# PoElli-Nucleo.net
KiCad netlist of a schematic drawn in EAGLE
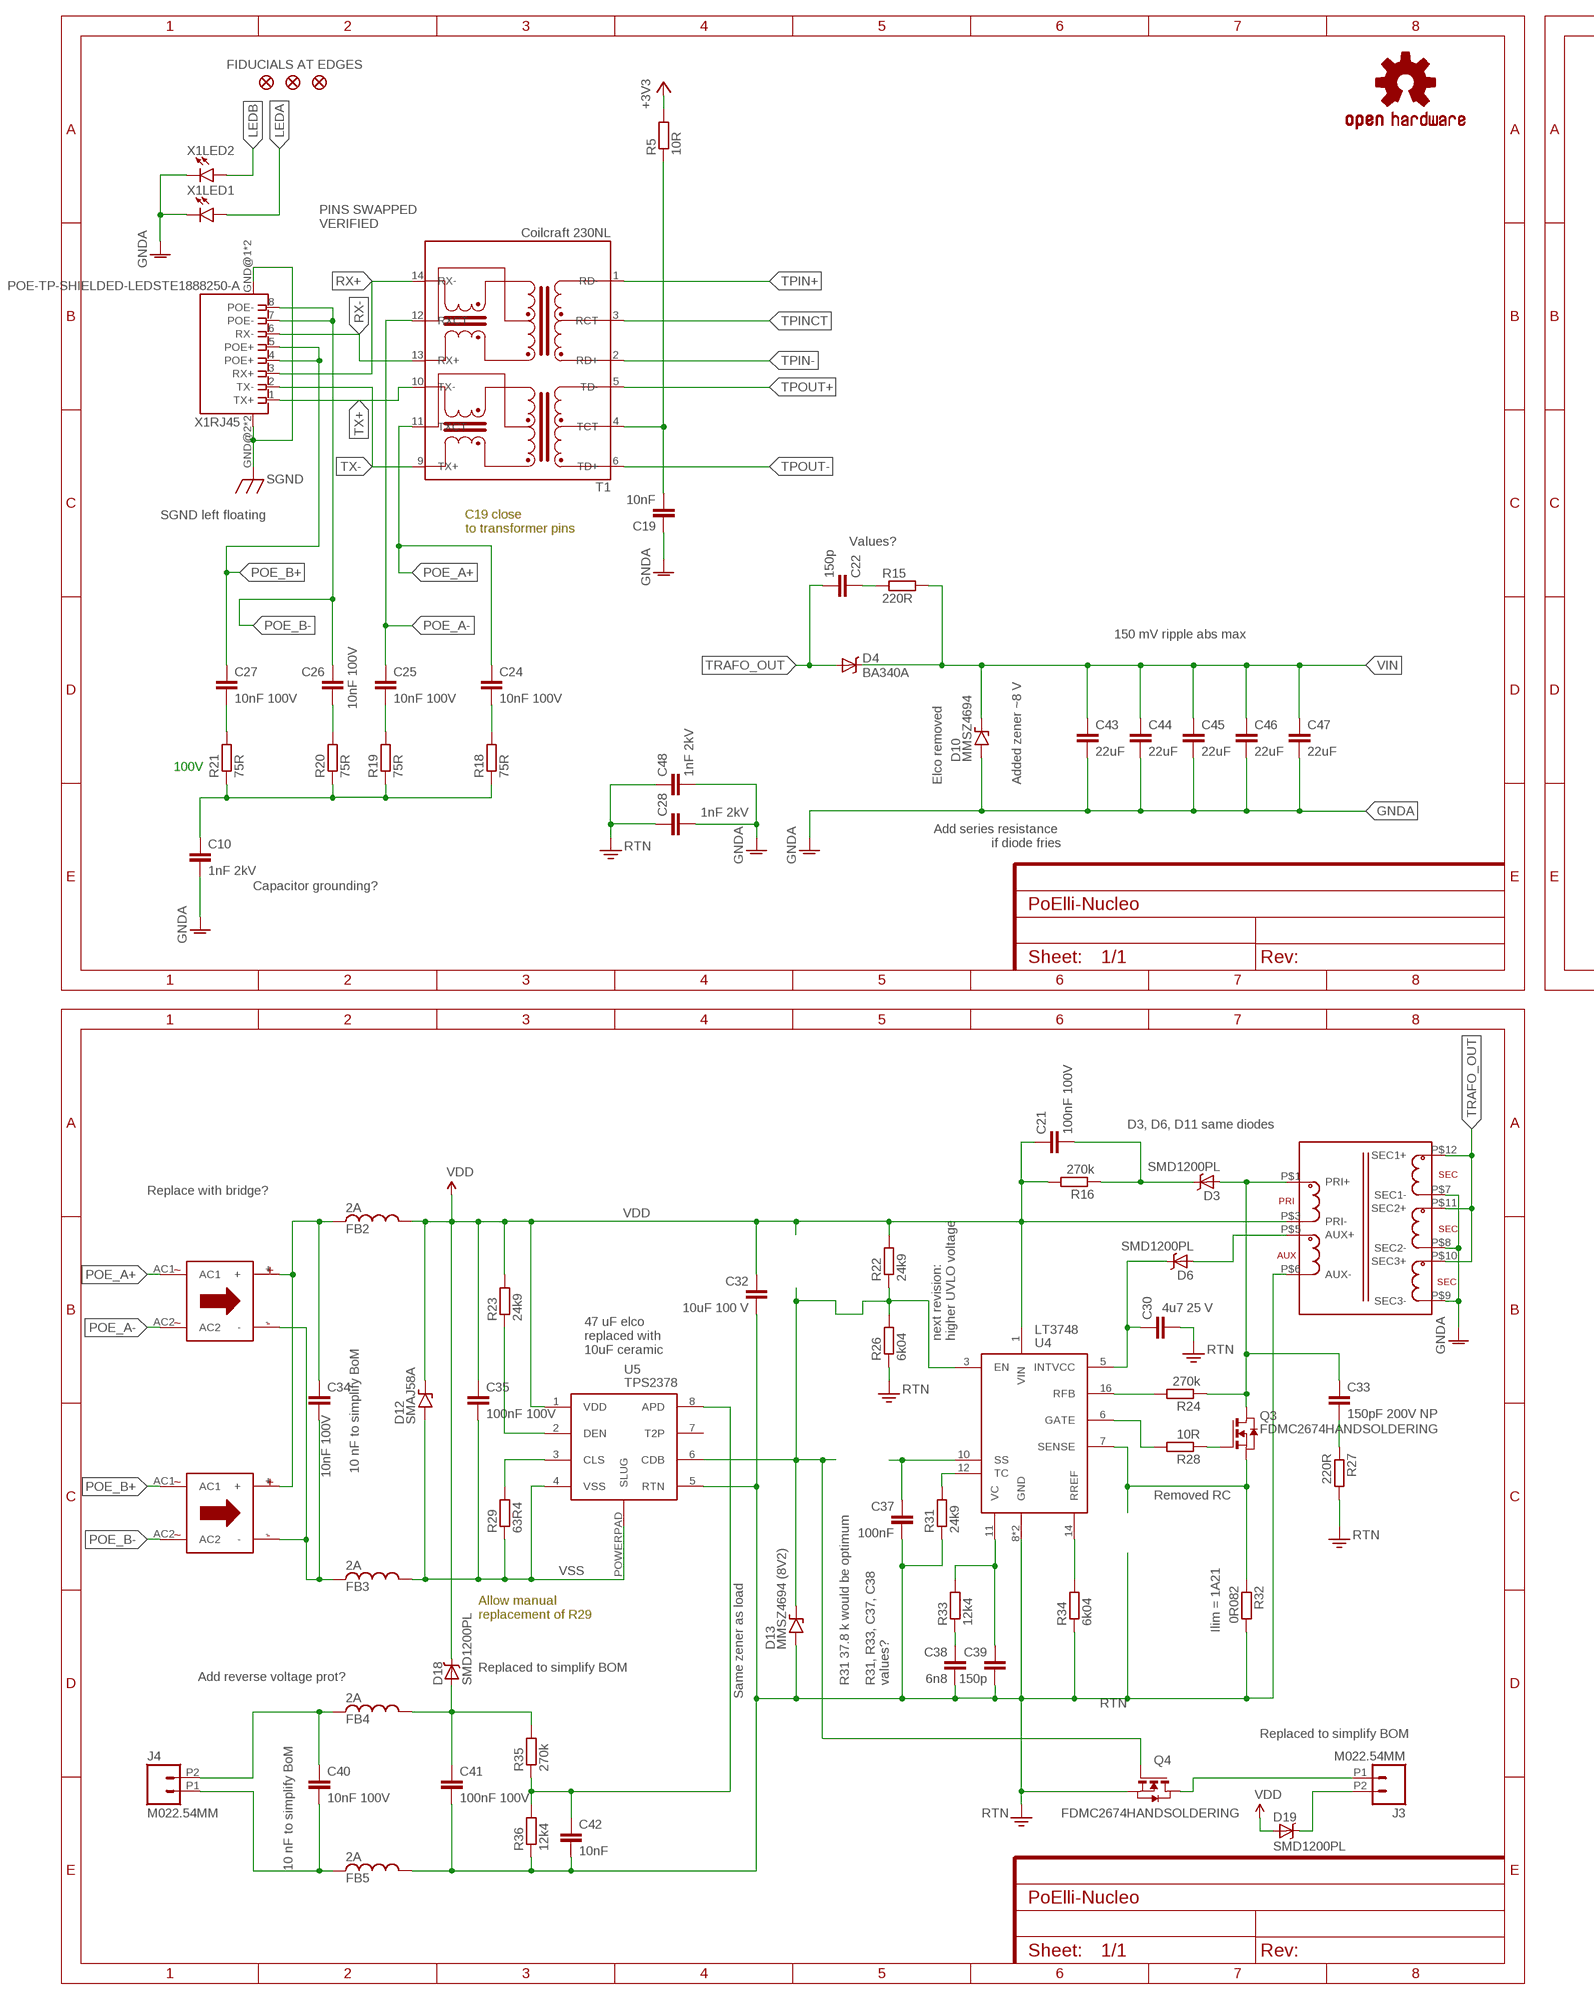
[diagram p0: schematic, sheet 1, part 1 of 2]
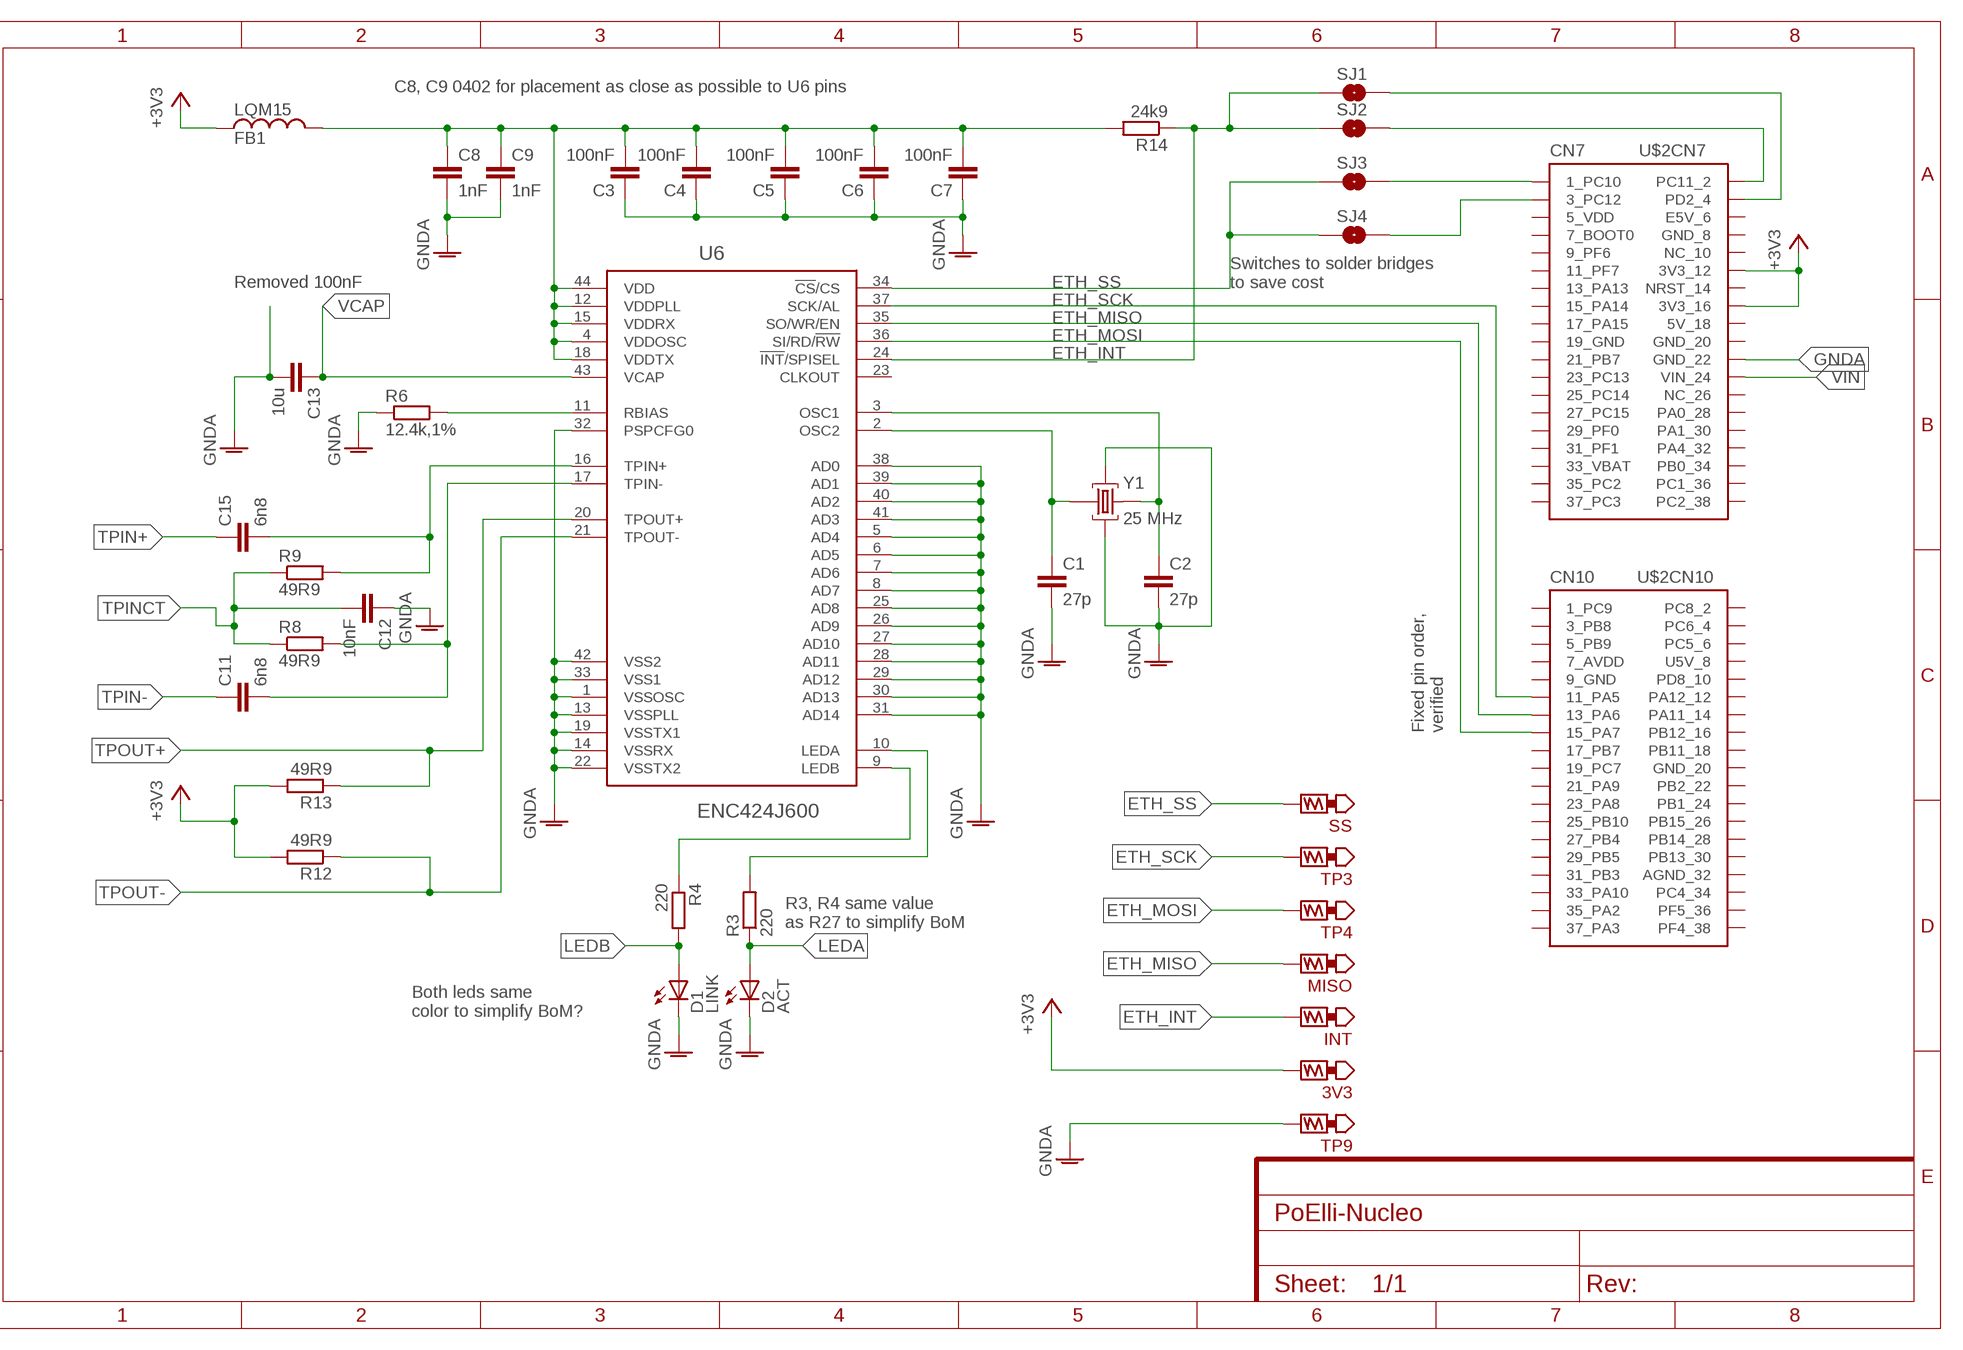
[diagram p1: schematic, sheet 1, part 2 of 2]

(export (version "E")
  (design (tool "Eeschema 10.0.6"))
  (components
    (comp (ref "3V3")
      (value "3V3")
      (footprint "eagle-import:TP_5000")
      (libsource (lib "eagle-import") (part "TEST_POINT-5000"))
    )
    (comp (ref "B1")
      (value "BRIDGE-RECTIFIER")
      (footprint "eagle-import:MBS1")
      (libsource (lib "eagle-import") (part "BRIDGE-RECTIFIER"))
    )
    (comp (ref "B2")
      (value "BRIDGE-RECTIFIER")
      (footprint "eagle-import:MBS1")
      (libsource (lib "eagle-import") (part "BRIDGE-RECTIFIER"))
    )
    (comp (ref "C1")
      (value "27p")
      (footprint "eagle-import:SMD0603-B")
      (libsource (lib "eagle-import") (part "C0603-B"))
    )
    (comp (ref "C2")
      (value "27p")
      (footprint "eagle-import:SMD0603-B")
      (libsource (lib "eagle-import") (part "C0603-B"))
    )
    (comp (ref "C3")
      (value "100nF")
      (footprint "eagle-import:SMD0603-B")
      (libsource (lib "eagle-import") (part "C0603-B"))
    )
    (comp (ref "C4")
      (value "100nF")
      (footprint "eagle-import:SMD0603-B")
      (libsource (lib "eagle-import") (part "C0603-B"))
    )
    (comp (ref "C5")
      (value "100nF")
      (footprint "eagle-import:SMD0603-B")
      (libsource (lib "eagle-import") (part "C0603-B"))
    )
    (comp (ref "C6")
      (value "100nF")
      (footprint "eagle-import:SMD0603-B")
      (libsource (lib "eagle-import") (part "C0603-B"))
    )
    (comp (ref "C7")
      (value "100nF")
      (footprint "eagle-import:SMD0603-B")
      (libsource (lib "eagle-import") (part "C0603-B"))
    )
    (comp (ref "C8")
      (value "1nF")
      (footprint "eagle-import:SMD0402-B")
      (libsource (lib "eagle-import") (part "C0402-B"))
    )
    (comp (ref "C9")
      (value "1nF")
      (footprint "eagle-import:SMD0402-B")
      (libsource (lib "eagle-import") (part "C0402-B"))
    )
    (comp (ref "C10")
      (value "1nF 2kV")
      (footprint "eagle-import:SMD1206-A")
      (libsource (lib "eagle-import") (part "C1206-A"))
    )
    (comp (ref "C11")
      (value "6n8")
      (footprint "eagle-import:SMD0603-B")
      (libsource (lib "eagle-import") (part "C0603-B"))
    )
    (comp (ref "C12")
      (value "10nF")
      (footprint "eagle-import:SMD0603-B")
      (libsource (lib "eagle-import") (part "C0603-B"))
    )
    (comp (ref "C13")
      (value "10u")
      (footprint "eagle-import:SMD0603-B")
      (libsource (lib "eagle-import") (part "C0603-B"))
    )
    (comp (ref "C15")
      (value "6n8")
      (footprint "eagle-import:SMD0603-B")
      (libsource (lib "eagle-import") (part "C0603-B"))
    )
    (comp (ref "C19")
      (value "10nF")
      (footprint "eagle-import:SMD0603-B")
      (libsource (lib "eagle-import") (part "C0603-B"))
    )
    (comp (ref "C21")
      (value "100nF 100V")
      (footprint "eagle-import:SMD0603-B")
      (libsource (lib "eagle-import") (part "C0603-B"))
    )
    (comp (ref "C22")
      (value "150p")
      (footprint "eagle-import:SMD0603-B")
      (libsource (lib "eagle-import") (part "C0603-B"))
    )
    (comp (ref "C24")
      (value "10nF 100V")
      (footprint "eagle-import:SMD0603-B")
      (libsource (lib "eagle-import") (part "C0603-B"))
    )
    (comp (ref "C25")
      (value "10nF 100V")
      (footprint "eagle-import:SMD0603-B")
      (libsource (lib "eagle-import") (part "C0603-B"))
    )
    (comp (ref "C26")
      (value "10nF 100V")
      (footprint "eagle-import:SMD0603-B")
      (libsource (lib "eagle-import") (part "C0603-B"))
    )
    (comp (ref "C27")
      (value "10nF 100V")
      (footprint "eagle-import:SMD0603-B")
      (libsource (lib "eagle-import") (part "C0603-B"))
    )
    (comp (ref "C28")
      (value "1nF 2kV")
      (footprint "eagle-import:SMD1206-A")
      (libsource (lib "eagle-import") (part "C1206-A"))
    )
    (comp (ref "C30")
      (value "4u7 25 V")
      (footprint "eagle-import:SMD0603-B")
      (libsource (lib "eagle-import") (part "C0603-B"))
    )
    (comp (ref "C32")
      (value "10uF 100 V")
      (footprint "eagle-import:SMD2220-REFLOW")
      (libsource (lib "eagle-import") (part "C2220-REFLOW"))
    )
    (comp (ref "C33")
      (value "150pF 200V NP")
      (footprint "eagle-import:SMD0603-B")
      (libsource (lib "eagle-import") (part "C0603-B"))
    )
    (comp (ref "C34")
      (value "10nF 100V")
      (footprint "eagle-import:SMD0603-B")
      (libsource (lib "eagle-import") (part "C0603-B"))
    )
    (comp (ref "C35")
      (value "100nF 100V")
      (footprint "eagle-import:SMD0603-B")
      (libsource (lib "eagle-import") (part "C0603-B"))
    )
    (comp (ref "C37")
      (value "100nF")
      (footprint "eagle-import:SMD0603-B")
      (libsource (lib "eagle-import") (part "C0603-B"))
    )
    (comp (ref "C38")
      (value "6n8")
      (footprint "eagle-import:SMD0603-B")
      (libsource (lib "eagle-import") (part "C0603-B"))
    )
    (comp (ref "C39")
      (value "150p")
      (footprint "eagle-import:SMD0603-B")
      (libsource (lib "eagle-import") (part "C0603-B"))
    )
    (comp (ref "C40")
      (value "10nF 100V")
      (footprint "eagle-import:SMD0603-B")
      (libsource (lib "eagle-import") (part "C0603-B"))
    )
    (comp (ref "C41")
      (value "100nF 100V")
      (footprint "eagle-import:SMD0603-B")
      (libsource (lib "eagle-import") (part "C0603-B"))
    )
    (comp (ref "C42")
      (value "10nF")
      (footprint "eagle-import:SMD0603-B")
      (libsource (lib "eagle-import") (part "C0603-B"))
    )
    (comp (ref "C43")
      (value "22uF")
      (footprint "eagle-import:SMD1206-A")
      (libsource (lib "eagle-import") (part "C1206-A"))
    )
    (comp (ref "C44")
      (value "22uF")
      (footprint "eagle-import:SMD1206-A")
      (libsource (lib "eagle-import") (part "C1206-A"))
    )
    (comp (ref "C45")
      (value "22uF")
      (footprint "eagle-import:SMD1206-A")
      (libsource (lib "eagle-import") (part "C1206-A"))
    )
    (comp (ref "C46")
      (value "22uF")
      (footprint "eagle-import:SMD1206-A")
      (libsource (lib "eagle-import") (part "C1206-A"))
    )
    (comp (ref "C47")
      (value "22uF")
      (footprint "eagle-import:SMD1206-A")
      (libsource (lib "eagle-import") (part "C1206-A"))
    )
    (comp (ref "C48")
      (value "1nF 2kV")
      (footprint "eagle-import:SMD1206-A")
      (libsource (lib "eagle-import") (part "C1206-A"))
    )
    (comp (ref "D1")
      (value "LINK")
      (footprint "eagle-import:LED-0603")
      (libsource (lib "eagle-import") (part "LED-GREEN0603"))
    )
    (comp (ref "D2")
      (value "ACT")
      (footprint "eagle-import:LED-0603")
      (libsource (lib "eagle-import") (part "LED-YELLOW0603"))
    )
    (comp (ref "D3")
      (value "SMD1200PL")
      (footprint "eagle-import:SOD-123FL-A")
      (libsource (lib "eagle-import") (part "SMD1XXPL"))
    )
    (comp (ref "D4")
      (value "BA340A")
      (footprint "eagle-import:SMA-DIODE")
      (libsource (lib "eagle-import") (part "B340A"))
    )
    (comp (ref "D6")
      (value "SMD1200PL")
      (footprint "eagle-import:SOD-123FL-A")
      (libsource (lib "eagle-import") (part "SMD1XXPL"))
    )
    (comp (ref "D10")
      (value "MMSZ4694")
      (footprint "eagle-import:SOD-123FL-A")
      (libsource (lib "eagle-import") (part "MMSZ4XXX"))
    )
    (comp (ref "D12")
      (value "SMAJ58A")
      (footprint "eagle-import:SMA")
      (libsource (lib "eagle-import") (part "SMAJ58A"))
    )
    (comp (ref "D13")
      (value "MMSZ4694 (8V2)")
      (footprint "eagle-import:SOD-123FL-A")
      (libsource (lib "eagle-import") (part "MMSZ4XXX"))
    )
    (comp (ref "D18")
      (value "SMD1200PL")
      (footprint "eagle-import:SOD-123FL-A")
      (libsource (lib "eagle-import") (part "SMD1XXPL"))
    )
    (comp (ref "D19")
      (value "SMD1200PL")
      (footprint "eagle-import:SOD-123FL-A")
      (libsource (lib "eagle-import") (part "SMD1XXPL"))
    )
    (comp (ref "FB1")
      (value "LQM15")
      (footprint "eagle-import:SMD0603-A")
      (libsource (lib "eagle-import") (part "FB-0603-A"))
    )
    (comp (ref "FB2")
      (value "2A")
      (footprint "eagle-import:SMD0603-A")
      (libsource (lib "eagle-import") (part "FB-0603-A"))
    )
    (comp (ref "FB3")
      (value "2A")
      (footprint "eagle-import:SMD0603-A")
      (libsource (lib "eagle-import") (part "FB-0603-A"))
    )
    (comp (ref "FB4")
      (value "2A")
      (footprint "eagle-import:SMD0603-A")
      (libsource (lib "eagle-import") (part "FB-0603-A"))
    )
    (comp (ref "FB5")
      (value "2A")
      (footprint "eagle-import:SMD0603-A")
      (libsource (lib "eagle-import") (part "FB-0603-A"))
    )
    (comp (ref "FID1")
      (value "FIDUCIAL1X2")
      (footprint "eagle-import:FIDUCIAL-1X2")
      (libsource (lib "eagle-import") (part "FIDUCIAL1X2"))
    )
    (comp (ref "FID2")
      (value "FIDUCIAL1X2")
      (footprint "eagle-import:FIDUCIAL-1X2")
      (libsource (lib "eagle-import") (part "FIDUCIAL1X2"))
    )
    (comp (ref "FID3")
      (value "FIDUCIAL1X2")
      (footprint "eagle-import:FIDUCIAL-1X2")
      (libsource (lib "eagle-import") (part "FIDUCIAL1X2"))
    )
    (comp (ref "INT")
      (value "TEST_POINT-5000")
      (footprint "eagle-import:TP_5000")
      (libsource (lib "eagle-import") (part "TEST_POINT-5000"))
    )
    (comp (ref "J3")
      (value "M022.54MM")
      (footprint "eagle-import:1X02_2.54_SCREWTERM")
      (libsource (lib "eagle-import") (part "M022.54MM_SCREWTERM"))
    )
    (comp (ref "J4")
      (value "M022.54MM")
      (footprint "eagle-import:1X02_2.54_SCREWTERM")
      (libsource (lib "eagle-import") (part "M022.54MM_SCREWTERM"))
    )
    (comp (ref "LOGO1")
      (value "OSHW-LOGOM")
      (footprint "eagle-import:OSHW-LOGO-M")
      (libsource (lib "eagle-import") (part "OSHW-LOGOM"))
    )
    (comp (ref "MISO")
      (value "MISO")
      (footprint "eagle-import:TP_5021")
      (libsource (lib "eagle-import") (part "TEST_POINT-5021"))
    )
    (comp (ref "Q3")
      (value "FDMC2674HANDSOLDERING")
      (footprint "eagle-import:MLP8L33_HS")
      (libsource (lib "eagle-import") (part "FDMC2674HANDSOLDERING"))
    )
    (comp (ref "Q4")
      (value "FDMC2674HANDSOLDERING")
      (footprint "eagle-import:MLP8L33_HS")
      (libsource (lib "eagle-import") (part "FDMC2674HANDSOLDERING"))
    )
    (comp (ref "R3")
      (value "220")
      (footprint "eagle-import:SMD0603-A")
      (libsource (lib "eagle-import") (part "R0603-A"))
    )
    (comp (ref "R4")
      (value "220")
      (footprint "eagle-import:SMD0603-A")
      (libsource (lib "eagle-import") (part "R0603-A"))
    )
    (comp (ref "R5")
      (value "10R")
      (footprint "eagle-import:SMD0603-B")
      (libsource (lib "eagle-import") (part "R0603-B"))
    )
    (comp (ref "R6")
      (value "12.4k,1%")
      (footprint "eagle-import:SMD0603-B")
      (libsource (lib "eagle-import") (part "R0603-B"))
    )
    (comp (ref "R8")
      (value "49R9")
      (footprint "eagle-import:SMD0603-B")
      (libsource (lib "eagle-import") (part "R0603-B"))
    )
    (comp (ref "R9")
      (value "49R9")
      (footprint "eagle-import:SMD0603-B")
      (libsource (lib "eagle-import") (part "R0603-B"))
    )
    (comp (ref "R12")
      (value "49R9")
      (footprint "eagle-import:SMD0603-B")
      (libsource (lib "eagle-import") (part "R0603-B"))
    )
    (comp (ref "R13")
      (value "49R9")
      (footprint "eagle-import:SMD0603-B")
      (libsource (lib "eagle-import") (part "R0603-B"))
    )
    (comp (ref "R14")
      (value "24k9")
      (footprint "eagle-import:SMD0603-A")
      (libsource (lib "eagle-import") (part "R0603-A"))
    )
    (comp (ref "R15")
      (value "220R")
      (footprint "eagle-import:SMD0603-B")
      (libsource (lib "eagle-import") (part "R0603-B"))
    )
    (comp (ref "R16")
      (value "270k")
      (footprint "eagle-import:SMD0603-A")
      (libsource (lib "eagle-import") (part "R0603-A"))
    )
    (comp (ref "R18")
      (value "75R")
      (footprint "eagle-import:SMD0603-B")
      (libsource (lib "eagle-import") (part "R0603-B"))
    )
    (comp (ref "R19")
      (value "75R")
      (footprint "eagle-import:SMD0603-B")
      (libsource (lib "eagle-import") (part "R0603-B"))
    )
    (comp (ref "R20")
      (value "75R")
      (footprint "eagle-import:SMD0603-B")
      (libsource (lib "eagle-import") (part "R0603-B"))
    )
    (comp (ref "R21")
      (value "75R")
      (footprint "eagle-import:SMD0603-B")
      (libsource (lib "eagle-import") (part "R0603-B"))
    )
    (comp (ref "R22")
      (value "24k9")
      (footprint "eagle-import:SMD0603-B")
      (libsource (lib "eagle-import") (part "R0603-B"))
    )
    (comp (ref "R23")
      (value "24k9")
      (footprint "eagle-import:SMD0603-B")
      (libsource (lib "eagle-import") (part "R0603-B"))
    )
    (comp (ref "R24")
      (value "270k")
      (footprint "eagle-import:SMD0603-B")
      (libsource (lib "eagle-import") (part "R0603-B"))
    )
    (comp (ref "R26")
      (value "6k04")
      (footprint "eagle-import:SMD0603-B")
      (libsource (lib "eagle-import") (part "R0603-B"))
    )
    (comp (ref "R27")
      (value "220R")
      (footprint "eagle-import:SMD0603-B")
      (libsource (lib "eagle-import") (part "R0603-B"))
    )
    (comp (ref "R28")
      (value "10R")
      (footprint "eagle-import:SMD0603-B")
      (libsource (lib "eagle-import") (part "R0603-B"))
    )
    (comp (ref "R29")
      (value "63R4")
      (footprint "eagle-import:SMD0603-B")
      (libsource (lib "eagle-import") (part "R0603-B"))
    )
    (comp (ref "R31")
      (value "24k9")
      (footprint "eagle-import:SMD0603-B")
      (libsource (lib "eagle-import") (part "R0603-B"))
    )
    (comp (ref "R32")
      (value "0R082")
      (footprint "eagle-import:SMD0603-B")
      (libsource (lib "eagle-import") (part "R0603-B"))
    )
    (comp (ref "R33")
      (value "12k4")
      (footprint "eagle-import:SMD0603-B")
      (libsource (lib "eagle-import") (part "R0603-B"))
    )
    (comp (ref "R34")
      (value "6k04")
      (footprint "eagle-import:SMD0603-B")
      (libsource (lib "eagle-import") (part "R0603-B"))
    )
    (comp (ref "R35")
      (value "270k")
      (footprint "eagle-import:SMD0603-B")
      (libsource (lib "eagle-import") (part "R0603-B"))
    )
    (comp (ref "R36")
      (value "12k4")
      (footprint "eagle-import:SMD0603-B")
      (libsource (lib "eagle-import") (part "R0603-B"))
    )
    (comp (ref "SJ1")
      (value "SOLDERJUMPERNC2")
      (footprint "eagle-import:SJ_2S-NOTRACE")
      (libsource (lib "eagle-import") (part "SOLDERJUMPERNC2"))
    )
    (comp (ref "SJ2")
      (value "SOLDERJUMPERNO")
      (footprint "eagle-import:SJ_2S-NO")
      (libsource (lib "eagle-import") (part "SOLDERJUMPERNO"))
    )
    (comp (ref "SJ3")
      (value "SOLDERJUMPERNC2")
      (footprint "eagle-import:SJ_2S-NOTRACE")
      (libsource (lib "eagle-import") (part "SOLDERJUMPERNC2"))
    )
    (comp (ref "SJ4")
      (value "SOLDERJUMPERNO")
      (footprint "eagle-import:SJ_2S-NO")
      (libsource (lib "eagle-import") (part "SOLDERJUMPERNO"))
    )
    (comp (ref "SS")
      (value "SS")
      (footprint "eagle-import:TP_5021")
      (libsource (lib "eagle-import") (part "TEST_POINT-5021"))
    )
    (comp (ref "T1")
      (value "Coilcraft 230NL")
      (footprint "eagle-import:COILCRAFT-ETH1-230L")
      (libsource (lib "eagle-import") (part "POE-ISOLATION-230NL"))
    )
    (comp (ref "T2")
      (value "FLYBACK-3_OUTPUTS_749119350")
      (footprint "eagle-import:WE_749119350")
      (libsource (lib "eagle-import") (part "FLYBACK-3_OUTPUTS_749119350"))
    )
    (comp (ref "TP3")
      (value "SCK")
      (footprint "eagle-import:TP_5021")
      (libsource (lib "eagle-import") (part "TEST_POINT-5021"))
    )
    (comp (ref "TP4")
      (value "MOSI")
      (footprint "eagle-import:TP_5021")
      (libsource (lib "eagle-import") (part "TEST_POINT-5021"))
    )
    (comp (ref "TP9")
      (value "GND")
      (footprint "eagle-import:TP_5000")
      (libsource (lib "eagle-import") (part "TEST_POINT-5000"))
    )
    (comp (ref "U$2")
      (value "NUCLEO-SHIELD-20PIN")
      (footprint "eagle-import:NUCLEO-SHIELD-UNDERSIDE-SHORT-20-PINHEADER")
      (libsource (lib "eagle-import") (part "NUCLEO-SHIELD-20PIN"))
    )
    (comp (ref "U4")
      (value "LT3748")
      (footprint "eagle-import:MSOP16(12)")
      (libsource (lib "eagle-import") (part "LT3748"))
    )
    (comp (ref "U5")
      (value "TPS2378")
      (footprint "eagle-import:SO08-POWERPAD")
      (libsource (lib "eagle-import") (part "TPS2378"))
    )
    (comp (ref "U6")
      (value "ENC424J600")
      (footprint "eagle-import:TQFP44-0.8MM")
      (libsource (lib "eagle-import") (part "ENC424J600"))
    )
    (comp (ref "X1")
      (value "POE-TP-SHIELDED-LEDSTE1888250-A")
      (footprint "eagle-import:TE1888250-A")
      (libsource (lib "eagle-import") (part "POE-TP-SHIELDED-LEDSTE1888250-A"))
    )
    (comp (ref "Y1")
      (value "25 MHz")
      (footprint "eagle-import:CRYSTAL-SMD-3225-GND")
      (libsource (lib "eagle-import") (part "CRYSTAL_WITH_GND"))
    )
  )
  (nets
    (net (code "1") (name "+3V3") (class "Default")
      (node (ref "3V3") (pin "P$1") (pinfunction "P$1_P$1") (pintype "passive"))
      (node (ref "FB1") (pin "P$1") (pinfunction "1_P$1") (pintype "passive"))
      (node (ref "R12") (pin "P$2") (pinfunction "2_P$2") (pintype "passive"))
      (node (ref "R13") (pin "P$2") (pinfunction "2_P$2") (pintype "passive"))
      (node (ref "R5") (pin "P$2") (pinfunction "2_P$2") (pintype "passive"))
      (node (ref "U$2") (pin "CN7_12") (pinfunction "3V3_12_CN7_12") (pintype "bidirectional"))
      (node (ref "U$2") (pin "CN7_16") (pinfunction "3V3_16_CN7_16") (pintype "bidirectional"))
    )
    (net (code "2") (name "/VSS") (class "Default")
      (node (ref "C35") (pin "P$2") (pinfunction "2_P$2") (pintype "passive"))
      (node (ref "D12") (pin "A") (pinfunction "A_A") (pintype "passive"))
      (node (ref "FB3") (pin "P$2") (pinfunction "2_P$2") (pintype "passive"))
      (node (ref "R29") (pin "P$1") (pinfunction "1_P$1") (pintype "passive"))
      (node (ref "U5") (pin "4") (pinfunction "VSS_4") (pintype "power_in"))
      (node (ref "U5") (pin "POWERPAD") (pinfunction "SLUG_POWERPAD") (pintype "power_in"))
    )
    (net (code "3") (name "ETH_INT") (class "Default")
      (node (ref "INT") (pin "P$1") (pinfunction "P$1_P$1") (pintype "passive"))
      (node (ref "R14") (pin "P$1") (pinfunction "1_P$1") (pintype "passive"))
      (node (ref "SJ1") (pin "1") (pinfunction "1_1") (pintype "passive"))
      (node (ref "SJ2") (pin "1") (pinfunction "1_1") (pintype "passive"))
      (node (ref "U6") (pin "24") (pinfunction "~{INT}/SPISEL_24") (pintype "bidirectional"))
    )
    (net (code "4") (name "ETH_MISO") (class "Default")
      (node (ref "MISO") (pin "P$1") (pinfunction "P$1_P$1") (pintype "passive"))
      (node (ref "U$2") (pin "CN10_13") (pinfunction "13_PA6_CN10_13") (pintype "bidirectional"))
      (node (ref "U6") (pin "35") (pinfunction "SO/WR/EN_35") (pintype "bidirectional"))
    )
    (net (code "5") (name "ETH_MOSI") (class "Default")
      (node (ref "TP4") (pin "P$1") (pinfunction "P$1_P$1") (pintype "passive"))
      (node (ref "U$2") (pin "CN10_15") (pinfunction "15_PA7_CN10_15") (pintype "bidirectional"))
      (node (ref "U6") (pin "36") (pinfunction "SI/RD/~{RW}_36") (pintype "input"))
    )
    (net (code "6") (name "ETH_SCK") (class "Default")
      (node (ref "TP3") (pin "P$1") (pinfunction "P$1_P$1") (pintype "passive"))
      (node (ref "U$2") (pin "CN10_11") (pinfunction "11_PA5_CN10_11") (pintype "bidirectional"))
      (node (ref "U6") (pin "37") (pinfunction "SCK/AL_37") (pintype "input"))
    )
    (net (code "7") (name "ETH_SS") (class "Default")
      (node (ref "SJ3") (pin "1") (pinfunction "1_1") (pintype "passive"))
      (node (ref "SJ4") (pin "1") (pinfunction "1_1") (pintype "passive"))
      (node (ref "SS") (pin "P$1") (pinfunction "P$1_P$1") (pintype "passive"))
      (node (ref "U6") (pin "34") (pinfunction "~{CS}/CS_34") (pintype "input"))
    )
    (net (code "8") (name "GNDA") (class "Default")
      (node (ref "C1") (pin "P$2") (pinfunction "2_P$2") (pintype "passive"))
      (node (ref "C10") (pin "P$2") (pinfunction "2_P$2") (pintype "passive"))
      (node (ref "C12") (pin "P$1") (pinfunction "1_P$1") (pintype "passive"))
      (node (ref "C13") (pin "P$2") (pinfunction "2_P$2") (pintype "passive"))
      (node (ref "C19") (pin "P$1") (pinfunction "1_P$1") (pintype "passive"))
      (node (ref "C2") (pin "P$2") (pinfunction "2_P$2") (pintype "passive"))
      (node (ref "C28") (pin "P$2") (pinfunction "2_P$2") (pintype "passive"))
      (node (ref "C3") (pin "P$1") (pinfunction "1_P$1") (pintype "passive"))
      (node (ref "C4") (pin "P$1") (pinfunction "1_P$1") (pintype "passive"))
      (node (ref "C43") (pin "P$2") (pinfunction "2_P$2") (pintype "passive"))
      (node (ref "C44") (pin "P$2") (pinfunction "2_P$2") (pintype "passive"))
      (node (ref "C45") (pin "P$2") (pinfunction "2_P$2") (pintype "passive"))
      (node (ref "C46") (pin "P$2") (pinfunction "2_P$2") (pintype "passive"))
      (node (ref "C47") (pin "P$2") (pinfunction "2_P$2") (pintype "passive"))
      (node (ref "C48") (pin "P$2") (pinfunction "2_P$2") (pintype "passive"))
      (node (ref "C5") (pin "P$1") (pinfunction "1_P$1") (pintype "passive"))
      (node (ref "C6") (pin "P$1") (pinfunction "1_P$1") (pintype "passive"))
      (node (ref "C7") (pin "P$1") (pinfunction "1_P$1") (pintype "passive"))
      (node (ref "C8") (pin "2") (pinfunction "2_2") (pintype "passive"))
      (node (ref "C9") (pin "2") (pinfunction "2_2") (pintype "passive"))
      (node (ref "D1") (pin "C") (pinfunction "C_C") (pintype "passive"))
      (node (ref "D10") (pin "A") (pinfunction "A_A") (pintype "passive"))
      (node (ref "D2") (pin "C") (pinfunction "C_C") (pintype "passive"))
      (node (ref "R6") (pin "P$1") (pinfunction "1_P$1") (pintype "passive"))
      (node (ref "T2") (pin "P$7") (pinfunction "SEC1-_P$7") (pintype "bidirectional"))
      (node (ref "T2") (pin "P$8") (pinfunction "SEC2-_P$8") (pintype "bidirectional"))
      (node (ref "T2") (pin "P$9") (pinfunction "SEC3-_P$9") (pintype "bidirectional"))
      (node (ref "TP9") (pin "P$1") (pinfunction "P$1_P$1") (pintype "passive"))
      (node (ref "U$2") (pin "CN7_22") (pinfunction "GND_22_CN7_22") (pintype "bidirectional"))
      (node (ref "U6") (pin "1") (pinfunction "VSSOSC_1") (pintype "power_in"))
      (node (ref "U6") (pin "13") (pinfunction "VSSPLL_13") (pintype "power_in"))
      (node (ref "U6") (pin "14") (pinfunction "VSSRX_14") (pintype "power_in"))
      (node (ref "U6") (pin "19") (pinfunction "VSSTX1_19") (pintype "power_in"))
      (node (ref "U6") (pin "22") (pinfunction "VSSTX2_22") (pintype "power_in"))
      (node (ref "U6") (pin "25") (pinfunction "AD8_25") (pintype "bidirectional"))
      (node (ref "U6") (pin "26") (pinfunction "AD9_26") (pintype "bidirectional"))
      (node (ref "U6") (pin "27") (pinfunction "AD10_27") (pintype "bidirectional"))
      (node (ref "U6") (pin "28") (pinfunction "AD11_28") (pintype "bidirectional"))
      (node (ref "U6") (pin "29") (pinfunction "AD12_29") (pintype "bidirectional"))
      (node (ref "U6") (pin "30") (pinfunction "AD13_30") (pintype "bidirectional"))
      (node (ref "U6") (pin "31") (pinfunction "AD14_31") (pintype "bidirectional"))
      (node (ref "U6") (pin "32") (pinfunction "PSPCFG0_32") (pintype "input"))
      (node (ref "U6") (pin "33") (pinfunction "VSS1_33") (pintype "power_in"))
      (node (ref "U6") (pin "38") (pinfunction "AD0_38") (pintype "bidirectional"))
      (node (ref "U6") (pin "39") (pinfunction "AD1_39") (pintype "bidirectional"))
      (node (ref "U6") (pin "40") (pinfunction "AD2_40") (pintype "bidirectional"))
      (node (ref "U6") (pin "41") (pinfunction "AD3_41") (pintype "bidirectional"))
      (node (ref "U6") (pin "42") (pinfunction "VSS2_42") (pintype "power_in"))
      (node (ref "U6") (pin "5") (pinfunction "AD4_5") (pintype "bidirectional"))
      (node (ref "U6") (pin "6") (pinfunction "AD5_6") (pintype "bidirectional"))
      (node (ref "U6") (pin "7") (pinfunction "AD6_7") (pintype "bidirectional"))
      (node (ref "U6") (pin "8") (pinfunction "AD7_8") (pintype "bidirectional"))
      (node (ref "X1") (pin "12") (pinfunction "C_12") (pintype "passive"))
      (node (ref "X1") (pin "9") (pinfunction "C_9") (pintype "passive"))
      (node (ref "Y1") (pin "2") (pinfunction "GND_2") (pintype "passive"))
      (node (ref "Y1") (pin "4") (pinfunction "GND_4") (pintype "passive"))
    )
    (net (code "9") (name "LEDA") (class "Default")
      (node (ref "D2") (pin "A") (pinfunction "A_A") (pintype "passive"))
      (node (ref "R3") (pin "P$1") (pinfunction "1_P$1") (pintype "passive"))
      (node (ref "X1") (pin "10") (pinfunction "A_10") (pintype "passive"))
    )
    (net (code "10") (name "LEDB") (class "Default")
      (node (ref "D1") (pin "A") (pinfunction "A_A") (pintype "passive"))
      (node (ref "R4") (pin "P$2") (pinfunction "2_P$2") (pintype "passive"))
      (node (ref "X1") (pin "11") (pinfunction "A_11") (pintype "passive"))
    )
    (net (code "11") (name "Net-(C1-1)") (class "Default")
      (node (ref "C1") (pin "P$1") (pinfunction "1_P$1") (pintype "passive"))
      (node (ref "U6") (pin "2") (pinfunction "OSC2_2") (pintype "output"))
      (node (ref "Y1") (pin "1") (pinfunction "C1_1") (pintype "passive"))
    )
    (net (code "12") (name "Net-(C2-1)") (class "Default")
      (node (ref "C2") (pin "P$1") (pinfunction "1_P$1") (pintype "passive"))
      (node (ref "U6") (pin "3") (pinfunction "OSC1_3") (pintype "input"))
      (node (ref "Y1") (pin "3") (pinfunction "C2_3") (pintype "passive"))
    )
    (net (code "13") (name "Net-(C3-2)") (class "Default")
      (node (ref "C3") (pin "P$2") (pinfunction "2_P$2") (pintype "passive"))
      (node (ref "C4") (pin "P$2") (pinfunction "2_P$2") (pintype "passive"))
      (node (ref "C5") (pin "P$2") (pinfunction "2_P$2") (pintype "passive"))
      (node (ref "C6") (pin "P$2") (pinfunction "2_P$2") (pintype "passive"))
      (node (ref "C7") (pin "P$2") (pinfunction "2_P$2") (pintype "passive"))
      (node (ref "C8") (pin "1") (pinfunction "1_1") (pintype "passive"))
      (node (ref "C9") (pin "1") (pinfunction "1_1") (pintype "passive"))
      (node (ref "FB1") (pin "P$2") (pinfunction "2_P$2") (pintype "passive"))
      (node (ref "R14") (pin "P$2") (pinfunction "2_P$2") (pintype "passive"))
      (node (ref "U6") (pin "12") (pinfunction "VDDPLL_12") (pintype "power_in"))
      (node (ref "U6") (pin "15") (pinfunction "VDDRX_15") (pintype "power_in"))
      (node (ref "U6") (pin "18") (pinfunction "VDDTX_18") (pintype "power_in"))
      (node (ref "U6") (pin "4") (pinfunction "VDDOSC_4") (pintype "power_in"))
      (node (ref "U6") (pin "44") (pinfunction "VDD_44") (pintype "power_in"))
    )
    (net (code "14") (name "Net-(C10-1)") (class "Default")
      (node (ref "C10") (pin "P$1") (pinfunction "1_P$1") (pintype "passive"))
      (node (ref "R18") (pin "P$1") (pinfunction "1_P$1") (pintype "passive"))
      (node (ref "R19") (pin "P$1") (pinfunction "1_P$1") (pintype "passive"))
      (node (ref "R20") (pin "P$1") (pinfunction "1_P$1") (pintype "passive"))
      (node (ref "R21") (pin "P$1") (pinfunction "1_P$1") (pintype "passive"))
    )
    (net (code "15") (name "Net-(C11-2)") (class "Default")
      (node (ref "C11") (pin "P$2") (pinfunction "2_P$2") (pintype "passive"))
      (node (ref "R8") (pin "P$2") (pinfunction "2_P$2") (pintype "passive"))
      (node (ref "U6") (pin "17") (pinfunction "TPIN-_17") (pintype "input"))
    )
    (net (code "16") (name "Net-(C15-2)") (class "Default")
      (node (ref "C15") (pin "P$2") (pinfunction "2_P$2") (pintype "passive"))
      (node (ref "R9") (pin "P$2") (pinfunction "2_P$2") (pintype "passive"))
      (node (ref "U6") (pin "16") (pinfunction "TPIN+_16") (pintype "input"))
    )
    (net (code "17") (name "Net-(C19-2)") (class "Default")
      (node (ref "C19") (pin "P$2") (pinfunction "2_P$2") (pintype "passive"))
      (node (ref "R5") (pin "P$1") (pinfunction "1_P$1") (pintype "passive"))
      (node (ref "T1") (pin "4") (pinfunction "TCT_4") (pintype "input"))
    )
    (net (code "18") (name "Net-(C21-2)") (class "Default")
      (node (ref "C21") (pin "P$2") (pinfunction "2_P$2") (pintype "passive"))
      (node (ref "D3") (pin "C") (pinfunction "C_C") (pintype "passive"))
      (node (ref "R16") (pin "P$1") (pinfunction "1_P$1") (pintype "passive"))
    )
    (net (code "19") (name "Net-(C22-1)") (class "Default")
      (node (ref "C22") (pin "P$1") (pinfunction "1_P$1") (pintype "passive"))
      (node (ref "R15") (pin "P$1") (pinfunction "1_P$1") (pintype "passive"))
    )
    (net (code "20") (name "Net-(C24-2)") (class "Default")
      (node (ref "C24") (pin "P$2") (pinfunction "2_P$2") (pintype "passive"))
      (node (ref "R18") (pin "P$2") (pinfunction "2_P$2") (pintype "passive"))
    )
    (net (code "21") (name "Net-(C25-2)") (class "Default")
      (node (ref "C25") (pin "P$2") (pinfunction "2_P$2") (pintype "passive"))
      (node (ref "R19") (pin "P$2") (pinfunction "2_P$2") (pintype "passive"))
    )
    (net (code "22") (name "Net-(C26-2)") (class "Default")
      (node (ref "C26") (pin "P$2") (pinfunction "2_P$2") (pintype "passive"))
      (node (ref "R20") (pin "P$2") (pinfunction "2_P$2") (pintype "passive"))
    )
    (net (code "23") (name "Net-(C27-2)") (class "Default")
      (node (ref "C27") (pin "P$2") (pinfunction "2_P$2") (pintype "passive"))
      (node (ref "R21") (pin "P$2") (pinfunction "2_P$2") (pintype "passive"))
    )
    (net (code "24") (name "Net-(C30-1)") (class "Default")
      (node (ref "C30") (pin "P$1") (pinfunction "1_P$1") (pintype "passive"))
      (node (ref "D6") (pin "C") (pinfunction "C_C") (pintype "passive"))
      (node (ref "U4") (pin "5") (pinfunction "INTVCC_5") (pintype "power_in"))
    )
    (net (code "25") (name "Net-(C33-1)") (class "Default")
      (node (ref "C33") (pin "P$1") (pinfunction "1_P$1") (pintype "passive"))
      (node (ref "D3") (pin "A") (pinfunction "A_A") (pintype "passive"))
      (node (ref "Q3") (pin "5") (pinfunction "D_5") (pintype "passive"))
      (node (ref "Q3") (pin "6") (pinfunction "D_6") (pintype "passive"))
      (node (ref "Q3") (pin "7") (pinfunction "D_7") (pintype "passive"))
      (node (ref "Q3") (pin "8") (pinfunction "D_8") (pintype "passive"))
      (node (ref "Q3") (pin "F1") (pinfunction "D_F1") (pintype "passive"))
      (node (ref "R24") (pin "P$1") (pinfunction "1_P$1") (pintype "passive"))
      (node (ref "T2") (pin "P$1") (pinfunction "PRI+_P$1") (pintype "bidirectional"))
    )
    (net (code "26") (name "Net-(C33-2)") (class "Default")
      (node (ref "C33") (pin "P$2") (pinfunction "2_P$2") (pintype "passive"))
      (node (ref "R27") (pin "P$1") (pinfunction "1_P$1") (pintype "passive"))
    )
    (net (code "27") (name "Net-(C34-1)") (class "Default")
      (node (ref "B1") (pin "+") (pinfunction "+_+") (pintype "power_in"))
      (node (ref "B2") (pin "+") (pinfunction "+_+") (pintype "power_in"))
      (node (ref "C34") (pin "P$1") (pinfunction "1_P$1") (pintype "passive"))
      (node (ref "FB2") (pin "P$1") (pinfunction "1_P$1") (pintype "passive"))
    )
    (net (code "28") (name "Net-(C34-2)") (class "Default")
      (node (ref "B1") (pin "-") (pinfunction "-_-") (pintype "power_in"))
      (node (ref "B2") (pin "-") (pinfunction "-_-") (pintype "power_in"))
      (node (ref "C34") (pin "P$2") (pinfunction "2_P$2") (pintype "passive"))
      (node (ref "FB3") (pin "P$1") (pinfunction "1_P$1") (pintype "passive"))
    )
    (net (code "29") (name "Net-(C37-1)") (class "Default")
      (node (ref "C37") (pin "P$1") (pinfunction "1_P$1") (pintype "passive"))
      (node (ref "U4") (pin "10") (pinfunction "SS_10") (pintype "bidirectional"))
    )
    (net (code "30") (name "Net-(C38-1)") (class "Default")
      (node (ref "C38") (pin "P$1") (pinfunction "1_P$1") (pintype "passive"))
      (node (ref "R33") (pin "P$1") (pinfunction "1_P$1") (pintype "passive"))
    )
    (net (code "31") (name "Net-(C39-1)") (class "Default")
      (node (ref "C39") (pin "P$1") (pinfunction "1_P$1") (pintype "passive"))
      (node (ref "R33") (pin "P$2") (pinfunction "2_P$2") (pintype "passive"))
      (node (ref "U4") (pin "11") (pinfunction "VC_11") (pintype "passive"))
    )
    (net (code "32") (name "Net-(C40-1)") (class "Default")
      (node (ref "C40") (pin "P$1") (pinfunction "1_P$1") (pintype "passive"))
      (node (ref "FB4") (pin "P$1") (pinfunction "1_P$1") (pintype "passive"))
      (node (ref "J4") (pin "P2") (pinfunction "2_P2") (pintype "passive"))
    )
    (net (code "33") (name "Net-(C40-2)") (class "Default")
      (node (ref "C40") (pin "P$2") (pinfunction "2_P$2") (pintype "passive"))
      (node (ref "FB5") (pin "P$1") (pinfunction "1_P$1") (pintype "passive"))
      (node (ref "J4") (pin "P1") (pinfunction "1_P1") (pintype "passive"))
    )
    (net (code "34") (name "Net-(C41-1)") (class "Default")
      (node (ref "C41") (pin "P$1") (pinfunction "1_P$1") (pintype "passive"))
      (node (ref "D18") (pin "A") (pinfunction "A_A") (pintype "passive"))
      (node (ref "FB4") (pin "P$2") (pinfunction "2_P$2") (pintype "passive"))
      (node (ref "R35") (pin "P$2") (pinfunction "2_P$2") (pintype "passive"))
    )
    (net (code "35") (name "Net-(C42-1)") (class "Default")
      (node (ref "C42") (pin "P$1") (pinfunction "1_P$1") (pintype "passive"))
      (node (ref "R35") (pin "P$1") (pinfunction "1_P$1") (pintype "passive"))
      (node (ref "R36") (pin "P$2") (pinfunction "2_P$2") (pintype "passive"))
      (node (ref "U5") (pin "8") (pinfunction "APD_8") (pintype "input"))
    )
    (net (code "36") (name "Net-(J3-1)") (class "Default")
      (node (ref "J3") (pin "P1") (pinfunction "1_P1") (pintype "passive"))
      (node (ref "Q4") (pin "5") (pinfunction "D_5") (pintype "passive"))
      (node (ref "Q4") (pin "6") (pinfunction "D_6") (pintype "passive"))
      (node (ref "Q4") (pin "7") (pinfunction "D_7") (pintype "passive"))
      (node (ref "Q4") (pin "8") (pinfunction "D_8") (pintype "passive"))
      (node (ref "Q4") (pin "F1") (pinfunction "D_F1") (pintype "passive"))
    )
    (net (code "37") (name "Net-(J3-2)") (class "Default")
      (node (ref "D19") (pin "C") (pinfunction "C_C") (pintype "passive"))
      (node (ref "J3") (pin "P2") (pinfunction "2_P2") (pintype "passive"))
    )
    (net (code "38") (name "Net-(Q3-G)") (class "Default")
      (node (ref "Q3") (pin "4") (pinfunction "G_4") (pintype "passive"))
      (node (ref "R28") (pin "P$1") (pinfunction "1_P$1") (pintype "passive"))
    )
    (net (code "39") (name "Net-(Q4-G)") (class "Default")
      (node (ref "D13") (pin "C") (pinfunction "C_C") (pintype "passive"))
      (node (ref "Q4") (pin "4") (pinfunction "G_4") (pintype "passive"))
      (node (ref "R22") (pin "P$1") (pinfunction "1_P$1") (pintype "passive"))
      (node (ref "R26") (pin "P$2") (pinfunction "2_P$2") (pintype "passive"))
      (node (ref "U4") (pin "3") (pinfunction "EN_3") (pintype "input"))
      (node (ref "U5") (pin "6") (pinfunction "CDB_6") (pintype "output"))
    )
    (net (code "40") (name "Net-(R3-2)") (class "Default")
      (node (ref "R3") (pin "P$2") (pinfunction "2_P$2") (pintype "passive"))
      (node (ref "U6") (pin "10") (pinfunction "LEDA_10") (pintype "output"))
    )
    (net (code "41") (name "Net-(R4-1)") (class "Default")
      (node (ref "R4") (pin "P$1") (pinfunction "1_P$1") (pintype "passive"))
      (node (ref "U6") (pin "9") (pinfunction "LEDB_9") (pintype "output"))
    )
    (net (code "42") (name "Net-(R6-2)") (class "Default")
      (node (ref "R6") (pin "P$2") (pinfunction "2_P$2") (pintype "passive"))
      (node (ref "U6") (pin "11") (pinfunction "RBIAS_11") (pintype "input"))
    )
    (net (code "43") (name "Net-(R23-1)") (class "Default")
      (node (ref "R23") (pin "P$1") (pinfunction "1_P$1") (pintype "passive"))
      (node (ref "U5") (pin "2") (pinfunction "DEN_2") (pintype "bidirectional"))
    )
    (net (code "44") (name "Net-(R24-2)") (class "Default")
      (node (ref "R24") (pin "P$2") (pinfunction "2_P$2") (pintype "passive"))
      (node (ref "U4") (pin "16") (pinfunction "RFB_16") (pintype "input"))
    )
    (net (code "45") (name "Net-(R28-2)") (class "Default")
      (node (ref "R28") (pin "P$2") (pinfunction "2_P$2") (pintype "passive"))
      (node (ref "U4") (pin "6") (pinfunction "GATE_6") (pintype "output"))
    )
    (net (code "46") (name "Net-(R29-2)") (class "Default")
      (node (ref "R29") (pin "P$2") (pinfunction "2_P$2") (pintype "passive"))
      (node (ref "U5") (pin "3") (pinfunction "CLS_3") (pintype "output"))
    )
    (net (code "47") (name "Net-(R31-2)") (class "Default")
      (node (ref "R31") (pin "P$2") (pinfunction "2_P$2") (pintype "passive"))
      (node (ref "U4") (pin "12") (pinfunction "TC_12") (pintype "output"))
    )
    (net (code "48") (name "Net-(R32-1)") (class "Default")
      (node (ref "Q3") (pin "1") (pinfunction "S_1") (pintype "passive"))
      (node (ref "Q3") (pin "2") (pinfunction "S_2") (pintype "passive"))
      (node (ref "Q3") (pin "3") (pinfunction "S_3") (pintype "passive"))
      (node (ref "R32") (pin "P$1") (pinfunction "1_P$1") (pintype "passive"))
      (node (ref "U4") (pin "7") (pinfunction "SENSE_7") (pintype "input"))
    )
    (net (code "49") (name "Net-(R34-2)") (class "Default")
      (node (ref "R34") (pin "P$2") (pinfunction "2_P$2") (pintype "passive"))
      (node (ref "U4") (pin "14") (pinfunction "RREF_14") (pintype "input"))
    )
    (net (code "50") (name "Net-(T2-AUX+)") (class "Default")
      (node (ref "D6") (pin "A") (pinfunction "A_A") (pintype "passive"))
      (node (ref "T2") (pin "P$5") (pinfunction "AUX+_P$5") (pintype "bidirectional"))
    )
    (net (code "51") (name "Net-(U$2B-1_PC10)") (class "Default")
      (node (ref "SJ3") (pin "2") (pinfunction "2_2") (pintype "passive"))
      (node (ref "U$2") (pin "CN7_1") (pinfunction "1_PC10_CN7_1") (pintype "bidirectional"))
    )
    (net (code "52") (name "Net-(U$2B-3_PC12)") (class "Default")
      (node (ref "SJ4") (pin "2") (pinfunction "2_2") (pintype "passive"))
      (node (ref "U$2") (pin "CN7_3") (pinfunction "3_PC12_CN7_3") (pintype "bidirectional"))
    )
    (net (code "53") (name "Net-(U$2B-PC11_2)") (class "Default")
      (node (ref "SJ2") (pin "2") (pinfunction "2_2") (pintype "passive"))
      (node (ref "U$2") (pin "CN7_2") (pinfunction "PC11_2_CN7_2") (pintype "bidirectional"))
    )
    (net (code "54") (name "Net-(U$2B-PD2_4)") (class "Default")
      (node (ref "SJ1") (pin "2") (pinfunction "2_2") (pintype "passive"))
      (node (ref "U$2") (pin "CN7_4") (pinfunction "PD2_4_CN7_4") (pintype "bidirectional"))
    )
    (net (code "55") (name "POE_A+") (class "Default")
      (node (ref "B1") (pin "AC1") (pinfunction "AC1_AC1") (pintype "input"))
      (node (ref "C24") (pin "P$1") (pinfunction "1_P$1") (pintype "passive"))
      (node (ref "T1") (pin "11") (pinfunction "TXCT_11") (pintype "bidirectional"))
    )
    (net (code "56") (name "POE_A-") (class "Default")
      (node (ref "B1") (pin "AC2") (pinfunction "AC2_AC2") (pintype "input"))
      (node (ref "C25") (pin "P$1") (pinfunction "1_P$1") (pintype "passive"))
      (node (ref "T1") (pin "12") (pinfunction "RXCT_12") (pintype "bidirectional"))
    )
    (net (code "57") (name "POE_B+") (class "Default")
      (node (ref "B2") (pin "AC1") (pinfunction "AC1_AC1") (pintype "input"))
      (node (ref "C27") (pin "P$1") (pinfunction "1_P$1") (pintype "passive"))
      (node (ref "X1") (pin "4") (pinfunction "POE+_4") (pintype "power_in"))
      (node (ref "X1") (pin "5") (pinfunction "POE+_5") (pintype "power_in"))
    )
    (net (code "58") (name "POE_B-") (class "Default")
      (node (ref "B2") (pin "AC2") (pinfunction "AC2_AC2") (pintype "input"))
      (node (ref "C26") (pin "P$1") (pinfunction "1_P$1") (pintype "passive"))
      (node (ref "X1") (pin "7") (pinfunction "POE-_7") (pintype "power_in"))
      (node (ref "X1") (pin "8") (pinfunction "POE-_8") (pintype "power_in"))
    )
    (net (code "59") (name "RTN") (class "Default")
      (node (ref "C28") (pin "P$1") (pinfunction "1_P$1") (pintype "passive"))
      (node (ref "C30") (pin "P$2") (pinfunction "2_P$2") (pintype "passive"))
      (node (ref "C32") (pin "P$2") (pinfunction "2_P$2") (pintype "passive"))
      (node (ref "C37") (pin "P$2") (pinfunction "2_P$2") (pintype "passive"))
      (node (ref "C38") (pin "P$2") (pinfunction "2_P$2") (pintype "passive"))
      (node (ref "C39") (pin "P$2") (pinfunction "2_P$2") (pintype "passive"))
      (node (ref "C41") (pin "P$2") (pinfunction "2_P$2") (pintype "passive"))
      (node (ref "C42") (pin "P$2") (pinfunction "2_P$2") (pintype "passive"))
      (node (ref "C48") (pin "P$1") (pinfunction "1_P$1") (pintype "passive"))
      (node (ref "D13") (pin "A") (pinfunction "A_A") (pintype "passive"))
      (node (ref "FB5") (pin "P$2") (pinfunction "2_P$2") (pintype "passive"))
      (node (ref "Q4") (pin "1") (pinfunction "S_1") (pintype "passive"))
      (node (ref "Q4") (pin "2") (pinfunction "S_2") (pintype "passive"))
      (node (ref "Q4") (pin "3") (pinfunction "S_3") (pintype "passive"))
      (node (ref "R26") (pin "P$1") (pinfunction "1_P$1") (pintype "passive"))
      (node (ref "R27") (pin "P$2") (pinfunction "2_P$2") (pintype "passive"))
      (node (ref "R31") (pin "P$1") (pinfunction "1_P$1") (pintype "passive"))
      (node (ref "R32") (pin "P$2") (pinfunction "2_P$2") (pintype "passive"))
      (node (ref "R34") (pin "P$1") (pinfunction "1_P$1") (pintype "passive"))
      (node (ref "R36") (pin "P$1") (pinfunction "1_P$1") (pintype "passive"))
      (node (ref "T2") (pin "P$6") (pinfunction "AUX-_P$6") (pintype "bidirectional"))
      (node (ref "U4") (pin "8") (pinfunction "GND_8") (pintype "power_in"))
      (node (ref "U4") (pin "9") (pinfunction "GND_9") (pintype "power_in"))
      (node (ref "U5") (pin "5") (pinfunction "RTN_5") (pintype "power_in"))
    )
    (net (code "60") (name "RX+") (class "Default")
      (node (ref "T1") (pin "14") (pinfunction "RX-_14") (pintype "bidirectional"))
      (node (ref "X1") (pin "3") (pinfunction "RX+_3") (pintype "output"))
    )
    (net (code "61") (name "RX-") (class "Default")
      (node (ref "T1") (pin "13") (pinfunction "RX+_13") (pintype "bidirectional"))
      (node (ref "X1") (pin "6") (pinfunction "RX-_6") (pintype "output"))
    )
    (net (code "62") (name "SGND") (class "Default")
      (node (ref "X1") (pin "GND@1") (pinfunction "GND_GND@1") (pintype "passive"))
      (node (ref "X1") (pin "GND@2") (pinfunction "GND_GND@2") (pintype "passive"))
      (node (ref "X1") (pin "GND@3") (pinfunction "GND_GND@3") (pintype "passive"))
      (node (ref "X1") (pin "GND@4") (pinfunction "GND_GND@4") (pintype "passive"))
    )
    (net (code "63") (name "TPIN+") (class "Default")
      (node (ref "C15") (pin "P$1") (pinfunction "1_P$1") (pintype "passive"))
      (node (ref "T1") (pin "1") (pinfunction "RD-_1") (pintype "input"))
    )
    (net (code "64") (name "TPIN-") (class "Default")
      (node (ref "C11") (pin "P$1") (pinfunction "1_P$1") (pintype "passive"))
      (node (ref "T1") (pin "2") (pinfunction "RD+_2") (pintype "input"))
    )
    (net (code "65") (name "TPINCT") (class "Default")
      (node (ref "C12") (pin "P$2") (pinfunction "2_P$2") (pintype "passive"))
      (node (ref "R8") (pin "P$1") (pinfunction "1_P$1") (pintype "passive"))
      (node (ref "R9") (pin "P$1") (pinfunction "1_P$1") (pintype "passive"))
      (node (ref "T1") (pin "3") (pinfunction "RCT_3") (pintype "input"))
    )
    (net (code "66") (name "TPOUT+") (class "Default")
      (node (ref "R13") (pin "P$1") (pinfunction "1_P$1") (pintype "passive"))
      (node (ref "T1") (pin "5") (pinfunction "TD-_5") (pintype "input"))
      (node (ref "U6") (pin "20") (pinfunction "TPOUT+_20") (pintype "output"))
    )
    (net (code "67") (name "TPOUT-") (class "Default")
      (node (ref "R12") (pin "P$1") (pinfunction "1_P$1") (pintype "passive"))
      (node (ref "T1") (pin "6") (pinfunction "TD+_6") (pintype "input"))
      (node (ref "U6") (pin "21") (pinfunction "TPOUT-_21") (pintype "output"))
    )
    (net (code "68") (name "TRAFO_OUT") (class "Default")
      (node (ref "C22") (pin "P$2") (pinfunction "2_P$2") (pintype "passive"))
      (node (ref "D4") (pin "A") (pinfunction "A_A") (pintype "passive"))
      (node (ref "T2") (pin "P$10") (pinfunction "SEC3+_P$10") (pintype "bidirectional"))
      (node (ref "T2") (pin "P$11") (pinfunction "SEC2+_P$11") (pintype "bidirectional"))
      (node (ref "T2") (pin "P$12") (pinfunction "SEC1+_P$12") (pintype "bidirectional"))
    )
    (net (code "69") (name "TX+") (class "Default")
      (node (ref "T1") (pin "10") (pinfunction "TX-_10") (pintype "bidirectional"))
      (node (ref "X1") (pin "1") (pinfunction "TX+_1") (pintype "input"))
    )
    (net (code "70") (name "TX-") (class "Default")
      (node (ref "T1") (pin "9") (pinfunction "TX+_9") (pintype "bidirectional"))
      (node (ref "X1") (pin "2") (pinfunction "TX-_2") (pintype "input"))
    )
    (net (code "71") (name "VCAP") (class "Default")
      (node (ref "C13") (pin "P$1") (pinfunction "1_P$1") (pintype "passive"))
      (node (ref "U6") (pin "43") (pinfunction "VCAP_43") (pintype "power_in"))
    )
    (net (code "72") (name "VDD") (class "Default")
      (node (ref "C21") (pin "P$1") (pinfunction "1_P$1") (pintype "passive"))
      (node (ref "C32") (pin "P$1") (pinfunction "1_P$1") (pintype "passive"))
      (node (ref "C35") (pin "P$1") (pinfunction "1_P$1") (pintype "passive"))
      (node (ref "D12") (pin "C") (pinfunction "C_C") (pintype "passive"))
      (node (ref "D18") (pin "C") (pinfunction "C_C") (pintype "passive"))
      (node (ref "D19") (pin "A") (pinfunction "A_A") (pintype "passive"))
      (node (ref "FB2") (pin "P$2") (pinfunction "2_P$2") (pintype "passive"))
      (node (ref "R16") (pin "P$2") (pinfunction "2_P$2") (pintype "passive"))
      (node (ref "R22") (pin "P$2") (pinfunction "2_P$2") (pintype "passive"))
      (node (ref "R23") (pin "P$2") (pinfunction "2_P$2") (pintype "passive"))
      (node (ref "T2") (pin "P$3") (pinfunction "PRI-_P$3") (pintype "bidirectional"))
      (node (ref "U4") (pin "1") (pinfunction "VIN_1") (pintype "power_in"))
      (node (ref "U5") (pin "1") (pinfunction "VDD_1") (pintype "input"))
    )
    (net (code "73") (name "VIN") (class "Default")
      (node (ref "C43") (pin "P$1") (pinfunction "1_P$1") (pintype "passive"))
      (node (ref "C44") (pin "P$1") (pinfunction "1_P$1") (pintype "passive"))
      (node (ref "C45") (pin "P$1") (pinfunction "1_P$1") (pintype "passive"))
      (node (ref "C46") (pin "P$1") (pinfunction "1_P$1") (pintype "passive"))
      (node (ref "C47") (pin "P$1") (pinfunction "1_P$1") (pintype "passive"))
      (node (ref "D10") (pin "C") (pinfunction "C_C") (pintype "passive"))
      (node (ref "D4") (pin "C") (pinfunction "C_C") (pintype "passive"))
      (node (ref "R15") (pin "P$2") (pinfunction "2_P$2") (pintype "passive"))
      (node (ref "U$2") (pin "CN7_24") (pinfunction "VIN_24_CN7_24") (pintype "bidirectional"))
    )
    (net (code "74") (name "unconnected-(U$2A-1_PC9-PadCN10_1)") (class "Default")
      (node (ref "U$2") (pin "CN10_1") (pinfunction "1_PC9_CN10_1") (pintype "bidirectional"))
    )
    (net (code "75") (name "unconnected-(U$2A-3_PB8-PadCN10_3)") (class "Default")
      (node (ref "U$2") (pin "CN10_3") (pinfunction "3_PB8_CN10_3") (pintype "bidirectional"))
    )
    (net (code "76") (name "unconnected-(U$2A-5_PB9-PadCN10_5)") (class "Default")
      (node (ref "U$2") (pin "CN10_5") (pinfunction "5_PB9_CN10_5") (pintype "bidirectional"))
    )
    (net (code "77") (name "unconnected-(U$2A-7_AVDD-PadCN10_7)") (class "Default")
      (node (ref "U$2") (pin "CN10_7") (pinfunction "7_AVDD_CN10_7") (pintype "bidirectional"))
    )
    (net (code "78") (name "unconnected-(U$2A-9_GND-PadCN10_9)") (class "Default")
      (node (ref "U$2") (pin "CN10_9") (pinfunction "9_GND_CN10_9") (pintype "bidirectional"))
    )
    (net (code "79") (name "unconnected-(U$2A-17_PB7-PadCN10_17)") (class "Default")
      (node (ref "U$2") (pin "CN10_17") (pinfunction "17_PB7_CN10_17") (pintype "bidirectional"))
    )
    (net (code "80") (name "unconnected-(U$2A-19_PC7-PadCN10_19)") (class "Default")
      (node (ref "U$2") (pin "CN10_19") (pinfunction "19_PC7_CN10_19") (pintype "bidirectional"))
    )
    (net (code "81") (name "unconnected-(U$2A-21_PA9-PadCN10_21)") (class "Default")
      (node (ref "U$2") (pin "CN10_21") (pinfunction "21_PA9_CN10_21") (pintype "bidirectional"))
    )
    (net (code "82") (name "unconnected-(U$2A-23_PA8-PadCN10_23)") (class "Default")
      (node (ref "U$2") (pin "CN10_23") (pinfunction "23_PA8_CN10_23") (pintype "bidirectional"))
    )
    (net (code "83") (name "unconnected-(U$2A-25_PB10-PadCN10_25)") (class "Default")
      (node (ref "U$2") (pin "CN10_25") (pinfunction "25_PB10_CN10_25") (pintype "bidirectional"))
    )
    (net (code "84") (name "unconnected-(U$2A-27_PB4-PadCN10_27)") (class "Default")
      (node (ref "U$2") (pin "CN10_27") (pinfunction "27_PB4_CN10_27") (pintype "bidirectional"))
    )
    (net (code "85") (name "unconnected-(U$2A-29_PB5-PadCN10_29)") (class "Default")
      (node (ref "U$2") (pin "CN10_29") (pinfunction "29_PB5_CN10_29") (pintype "bidirectional"))
    )
    (net (code "86") (name "unconnected-(U$2A-31_PB3-PadCN10_31)") (class "Default")
      (node (ref "U$2") (pin "CN10_31") (pinfunction "31_PB3_CN10_31") (pintype "bidirectional"))
    )
    (net (code "87") (name "unconnected-(U$2A-33_PA10-PadCN10_33)") (class "Default")
      (node (ref "U$2") (pin "CN10_33") (pinfunction "33_PA10_CN10_33") (pintype "bidirectional"))
    )
    (net (code "88") (name "unconnected-(U$2A-35_PA2-PadCN10_35)") (class "Default")
      (node (ref "U$2") (pin "CN10_35") (pinfunction "35_PA2_CN10_35") (pintype "bidirectional"))
    )
    (net (code "89") (name "unconnected-(U$2A-37_PA3-PadCN10_37)") (class "Default")
      (node (ref "U$2") (pin "CN10_37") (pinfunction "37_PA3_CN10_37") (pintype "bidirectional"))
    )
    (net (code "90") (name "unconnected-(U$2A-AGND_32-PadCN10_32)") (class "Default")
      (node (ref "U$2") (pin "CN10_32") (pinfunction "AGND_32_CN10_32") (pintype "bidirectional"))
    )
    (net (code "91") (name "unconnected-(U$2A-GND_20-PadCN10_20)") (class "Default")
      (node (ref "U$2") (pin "CN10_20") (pinfunction "GND_20_CN10_20") (pintype "bidirectional"))
    )
    (net (code "92") (name "unconnected-(U$2A-PA11_14-PadCN10_14)") (class "Default")
      (node (ref "U$2") (pin "CN10_14") (pinfunction "PA11_14_CN10_14") (pintype "bidirectional"))
    )
    (net (code "93") (name "unconnected-(U$2A-PA12_12-PadCN10_12)") (class "Default")
      (node (ref "U$2") (pin "CN10_12") (pinfunction "PA12_12_CN10_12") (pintype "bidirectional"))
    )
    (net (code "94") (name "unconnected-(U$2A-PB1_24-PadCN10_24)") (class "Default")
      (node (ref "U$2") (pin "CN10_24") (pinfunction "PB1_24_CN10_24") (pintype "bidirectional"))
    )
    (net (code "95") (name "unconnected-(U$2A-PB2_22-PadCN10_22)") (class "Default")
      (node (ref "U$2") (pin "CN10_22") (pinfunction "PB2_22_CN10_22") (pintype "bidirectional"))
    )
    (net (code "96") (name "unconnected-(U$2A-PB11_18-PadCN10_18)") (class "Default")
      (node (ref "U$2") (pin "CN10_18") (pinfunction "PB11_18_CN10_18") (pintype "bidirectional"))
    )
    (net (code "97") (name "unconnected-(U$2A-PB12_16-PadCN10_16)") (class "Default")
      (node (ref "U$2") (pin "CN10_16") (pinfunction "PB12_16_CN10_16") (pintype "bidirectional"))
    )
    (net (code "98") (name "unconnected-(U$2A-PB13_30-PadCN10_30)") (class "Default")
      (node (ref "U$2") (pin "CN10_30") (pinfunction "PB13_30_CN10_30") (pintype "bidirectional"))
    )
    (net (code "99") (name "unconnected-(U$2A-PB14_28-PadCN10_28)") (class "Default")
      (node (ref "U$2") (pin "CN10_28") (pinfunction "PB14_28_CN10_28") (pintype "bidirectional"))
    )
    (net (code "100") (name "unconnected-(U$2A-PB15_26-PadCN10_26)") (class "Default")
      (node (ref "U$2") (pin "CN10_26") (pinfunction "PB15_26_CN10_26") (pintype "bidirectional"))
    )
    (net (code "101") (name "unconnected-(U$2A-PC4_34-PadCN10_34)") (class "Default")
      (node (ref "U$2") (pin "CN10_34") (pinfunction "PC4_34_CN10_34") (pintype "bidirectional"))
    )
    (net (code "102") (name "unconnected-(U$2A-PC5_6-PadCN10_6)") (class "Default")
      (node (ref "U$2") (pin "CN10_6") (pinfunction "PC5_6_CN10_6") (pintype "bidirectional"))
    )
    (net (code "103") (name "unconnected-(U$2A-PC6_4-PadCN10_4)") (class "Default")
      (node (ref "U$2") (pin "CN10_4") (pinfunction "PC6_4_CN10_4") (pintype "bidirectional"))
    )
    (net (code "104") (name "unconnected-(U$2A-PC8_2-PadCN10_2)") (class "Default")
      (node (ref "U$2") (pin "CN10_2") (pinfunction "PC8_2_CN10_2") (pintype "bidirectional"))
    )
    (net (code "105") (name "unconnected-(U$2A-PD8_10-PadCN10_10)") (class "Default")
      (node (ref "U$2") (pin "CN10_10") (pinfunction "PD8_10_CN10_10") (pintype "bidirectional"))
    )
    (net (code "106") (name "unconnected-(U$2A-PF4_38-PadCN10_38)") (class "Default")
      (node (ref "U$2") (pin "CN10_38") (pinfunction "PF4_38_CN10_38") (pintype "bidirectional"))
    )
    (net (code "107") (name "unconnected-(U$2A-PF5_36-PadCN10_36)") (class "Default")
      (node (ref "U$2") (pin "CN10_36") (pinfunction "PF5_36_CN10_36") (pintype "bidirectional"))
    )
    (net (code "108") (name "unconnected-(U$2A-U5V_8-PadCN10_8)") (class "Default")
      (node (ref "U$2") (pin "CN10_8") (pinfunction "U5V_8_CN10_8") (pintype "bidirectional"))
    )
    (net (code "109") (name "unconnected-(U$2B-5V_18-PadCN7_18)") (class "Default")
      (node (ref "U$2") (pin "CN7_18") (pinfunction "5V_18_CN7_18") (pintype "bidirectional"))
    )
    (net (code "110") (name "unconnected-(U$2B-5_VDD-PadCN7_5)") (class "Default")
      (node (ref "U$2") (pin "CN7_5") (pinfunction "5_VDD_CN7_5") (pintype "bidirectional"))
    )
    (net (code "111") (name "unconnected-(U$2B-7_BOOT0-PadCN7_7)") (class "Default")
      (node (ref "U$2") (pin "CN7_7") (pinfunction "7_BOOT0_CN7_7") (pintype "bidirectional"))
    )
    (net (code "112") (name "unconnected-(U$2B-9_PF6-PadCN7_9)") (class "Default")
      (node (ref "U$2") (pin "CN7_9") (pinfunction "9_PF6_CN7_9") (pintype "bidirectional"))
    )
    (net (code "113") (name "unconnected-(U$2B-11_PF7-PadCN7_11)") (class "Default")
      (node (ref "U$2") (pin "CN7_11") (pinfunction "11_PF7_CN7_11") (pintype "bidirectional"))
    )
    (net (code "114") (name "unconnected-(U$2B-13_PA13-PadCN7_13)") (class "Default")
      (node (ref "U$2") (pin "CN7_13") (pinfunction "13_PA13_CN7_13") (pintype "bidirectional"))
    )
    (net (code "115") (name "unconnected-(U$2B-15_PA14-PadCN7_15)") (class "Default")
      (node (ref "U$2") (pin "CN7_15") (pinfunction "15_PA14_CN7_15") (pintype "bidirectional"))
    )
    (net (code "116") (name "unconnected-(U$2B-17_PA15-PadCN7_17)") (class "Default")
      (node (ref "U$2") (pin "CN7_17") (pinfunction "17_PA15_CN7_17") (pintype "bidirectional"))
    )
    (net (code "117") (name "unconnected-(U$2B-19_GND-PadCN7_19)") (class "Default")
      (node (ref "U$2") (pin "CN7_19") (pinfunction "19_GND_CN7_19") (pintype "bidirectional"))
    )
    (net (code "118") (name "unconnected-(U$2B-21_PB7-PadCN7_21)") (class "Default")
      (node (ref "U$2") (pin "CN7_21") (pinfunction "21_PB7_CN7_21") (pintype "bidirectional"))
    )
    (net (code "119") (name "unconnected-(U$2B-23_PC13-PadCN7_23)") (class "Default")
      (node (ref "U$2") (pin "CN7_23") (pinfunction "23_PC13_CN7_23") (pintype "bidirectional"))
    )
    (net (code "120") (name "unconnected-(U$2B-25_PC14-PadCN7_25)") (class "Default")
      (node (ref "U$2") (pin "CN7_25") (pinfunction "25_PC14_CN7_25") (pintype "bidirectional"))
    )
    (net (code "121") (name "unconnected-(U$2B-27_PC15-PadCN7_27)") (class "Default")
      (node (ref "U$2") (pin "CN7_27") (pinfunction "27_PC15_CN7_27") (pintype "bidirectional"))
    )
    (net (code "122") (name "unconnected-(U$2B-29_PF0-PadCN7_29)") (class "Default")
      (node (ref "U$2") (pin "CN7_29") (pinfunction "29_PF0_CN7_29") (pintype "bidirectional"))
    )
    (net (code "123") (name "unconnected-(U$2B-31_PF1-PadCN7_31)") (class "Default")
      (node (ref "U$2") (pin "CN7_31") (pinfunction "31_PF1_CN7_31") (pintype "bidirectional"))
    )
    (net (code "124") (name "unconnected-(U$2B-33_VBAT-PadCN7_33)") (class "Default")
      (node (ref "U$2") (pin "CN7_33") (pinfunction "33_VBAT_CN7_33") (pintype "bidirectional"))
    )
    (net (code "125") (name "unconnected-(U$2B-35_PC2-PadCN7_35)") (class "Default")
      (node (ref "U$2") (pin "CN7_35") (pinfunction "35_PC2_CN7_35") (pintype "bidirectional"))
    )
    (net (code "126") (name "unconnected-(U$2B-37_PC3-PadCN7_37)") (class "Default")
      (node (ref "U$2") (pin "CN7_37") (pinfunction "37_PC3_CN7_37") (pintype "bidirectional"))
    )
    (net (code "127") (name "unconnected-(U$2B-E5V_6-PadCN7_6)") (class "Default")
      (node (ref "U$2") (pin "CN7_6") (pinfunction "E5V_6_CN7_6") (pintype "bidirectional"))
    )
    (net (code "128") (name "unconnected-(U$2B-GND_8-PadCN7_8)") (class "Default")
      (node (ref "U$2") (pin "CN7_8") (pinfunction "GND_8_CN7_8") (pintype "bidirectional"))
    )
    (net (code "129") (name "unconnected-(U$2B-GND_20-PadCN7_20)") (class "Default")
      (node (ref "U$2") (pin "CN7_20") (pinfunction "GND_20_CN7_20") (pintype "bidirectional"))
    )
    (net (code "130") (name "unconnected-(U$2B-NC_10-PadCN7_10)") (class "Default")
      (node (ref "U$2") (pin "CN7_10") (pinfunction "NC_10_CN7_10") (pintype "bidirectional"))
    )
    (net (code "131") (name "unconnected-(U$2B-NC_26-PadCN7_26)") (class "Default")
      (node (ref "U$2") (pin "CN7_26") (pinfunction "NC_26_CN7_26") (pintype "bidirectional"))
    )
    (net (code "132") (name "unconnected-(U$2B-NRST_14-PadCN7_14)") (class "Default")
      (node (ref "U$2") (pin "CN7_14") (pinfunction "NRST_14_CN7_14") (pintype "bidirectional"))
    )
    (net (code "133") (name "unconnected-(U$2B-PA0_28-PadCN7_28)") (class "Default")
      (node (ref "U$2") (pin "CN7_28") (pinfunction "PA0_28_CN7_28") (pintype "bidirectional"))
    )
    (net (code "134") (name "unconnected-(U$2B-PA1_30-PadCN7_30)") (class "Default")
      (node (ref "U$2") (pin "CN7_30") (pinfunction "PA1_30_CN7_30") (pintype "bidirectional"))
    )
    (net (code "135") (name "unconnected-(U$2B-PA4_32-PadCN7_32)") (class "Default")
      (node (ref "U$2") (pin "CN7_32") (pinfunction "PA4_32_CN7_32") (pintype "bidirectional"))
    )
    (net (code "136") (name "unconnected-(U$2B-PB0_34-PadCN7_34)") (class "Default")
      (node (ref "U$2") (pin "CN7_34") (pinfunction "PB0_34_CN7_34") (pintype "bidirectional"))
    )
    (net (code "137") (name "unconnected-(U$2B-PC1_36-PadCN7_36)") (class "Default")
      (node (ref "U$2") (pin "CN7_36") (pinfunction "PC1_36_CN7_36") (pintype "bidirectional"))
    )
    (net (code "138") (name "unconnected-(U$2B-PC2_38-PadCN7_38)") (class "Default")
      (node (ref "U$2") (pin "CN7_38") (pinfunction "PC2_38_CN7_38") (pintype "bidirectional"))
    )
    (net (code "139") (name "unconnected-(U5-T2P-Pad7)") (class "Default")
      (node (ref "U5") (pin "7") (pinfunction "T2P_7") (pintype "output"))
    )
    (net (code "140") (name "unconnected-(U6-CLKOUT-Pad23)") (class "Default")
      (node (ref "U6") (pin "23") (pinfunction "CLKOUT_23") (pintype "output"))
    )
  )
)
